# slider.net
KiCad netlist of a schematic drawn in EAGLE
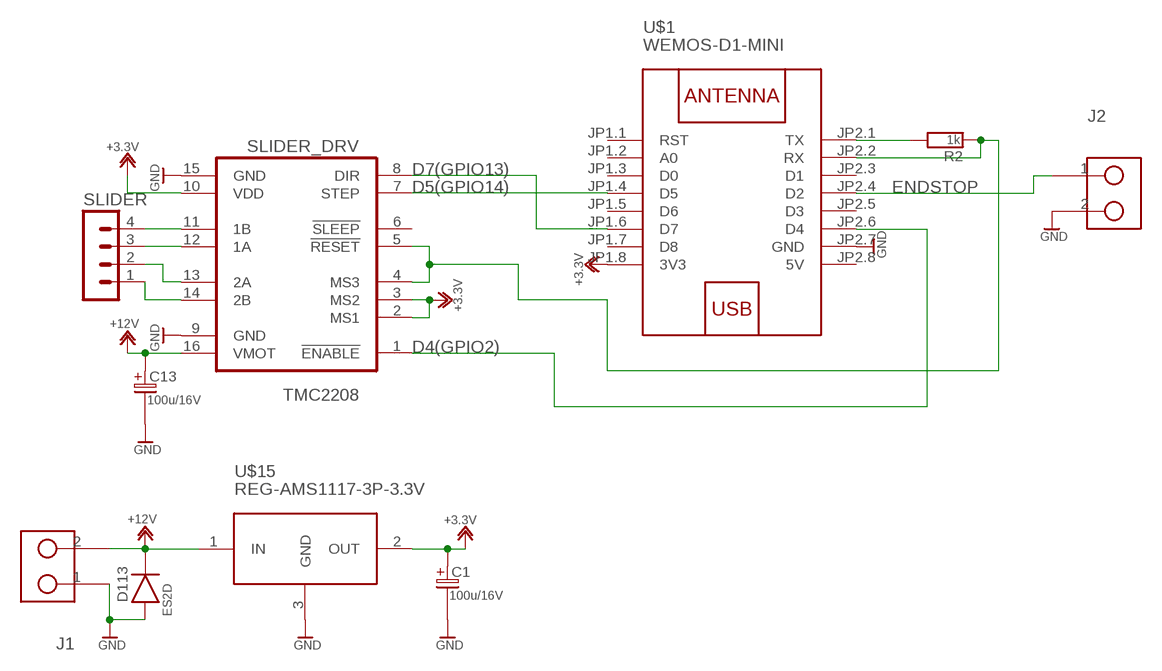
[diagram p0: schematic, sheet 1]

(export (version "E")
  (design (tool "Eeschema 10.0.6"))
  (components
    (comp (ref "C1")
      (value "100u/16V")
      (footprint "eagle-import:ES-3,5_8")
      (libsource (lib "eagle-import") (part "C-EL-3,5/8"))
    )
    (comp (ref "C13")
      (value "100u/16V")
      (footprint "eagle-import:ES-3,5_8")
      (libsource (lib "eagle-import") (part "C-EL-3,5/8"))
    )
    (comp (ref "D113")
      (value "ES2D")
      (footprint "eagle-import:SMB")
      (libsource (lib "eagle-import") (part "DIODESMB"))
    )
    (comp (ref "J1")
      (value "GMKDS-2")
      (footprint "eagle-import:GMKDS1,5")
      (libsource (lib "eagle-import") (part "GMKDS-2"))
    )
    (comp (ref "J2")
      (value "GMKDS-2")
      (footprint "eagle-import:GMKDS1,5")
      (libsource (lib "eagle-import") (part "GMKDS-2"))
    )
    (comp (ref "R2")
      (value "1k")
      (footprint "eagle-import:0805")
      (libsource (lib "eagle-import") (part "RES-0805"))
    )
    (comp (ref "SLIDER")
      (value "MA04-1")
      (footprint "eagle-import:MA04-1")
      (libsource (lib "eagle-import") (part "MA04-1"))
    )
    (comp (ref "SLIDER_DRV")
      (value "TMC2208")
      (footprint "eagle-import:POLOLULU2128")
      (libsource (lib "eagle-import") (part "POLOLULU2128"))
    )
    (comp (ref "U$1")
      (value "WEMOS-D1-MINI")
      (footprint "eagle-import:WEMOS-D1-MINI")
      (libsource (lib "eagle-import") (part "WEMOS-D1-MINI"))
    )
    (comp (ref "U$15")
      (value "REG-AMS1117-3P-3.3V")
      (footprint "eagle-import:REG-AMS1117-3P")
      (libsource (lib "eagle-import") (part "REG-AMS1117-3P-3.3V"))
    )
  )
  (nets
    (net (code "1") (name "+3.3V") (class "Default")
      (node (ref "C1") (pin "1") (pinfunction "1_1") (pintype "passive"))
      (node (ref "SLIDER_DRV") (pin "10") (pinfunction "VDD_10") (pintype "power_in"))
      (node (ref "SLIDER_DRV") (pin "2") (pinfunction "MS1_2") (pintype "input"))
      (node (ref "SLIDER_DRV") (pin "3") (pinfunction "MS2_3") (pintype "input"))
      (node (ref "U$1") (pin "JP1.8") (pinfunction "3V3_JP1.8") (pintype "power_in"))
      (node (ref "U$15") (pin "2") (pinfunction "OUT_2") (pintype "bidirectional"))
    )
    (net (code "2") (name "+12V") (class "Default")
      (node (ref "C13") (pin "1") (pinfunction "1_1") (pintype "passive"))
      (node (ref "D113") (pin "2") (pinfunction "K_2") (pintype "passive"))
      (node (ref "J1") (pin "2") (pinfunction "2_2") (pintype "passive"))
      (node (ref "SLIDER_DRV") (pin "16") (pinfunction "VMOT_16") (pintype "power_in"))
      (node (ref "U$15") (pin "1") (pinfunction "IN_1") (pintype "bidirectional"))
    )
    (net (code "3") (name "/5V") (class "Default")
      (node (ref "U$1") (pin "JP2.8") (pinfunction "5V_JP2.8") (pintype "power_in"))
    )
    (net (code "4") (name "/D4(GPIO2)") (class "Default")
      (node (ref "SLIDER_DRV") (pin "1") (pinfunction "~{ENABLE}_1") (pintype "input"))
      (node (ref "U$1") (pin "JP2.6") (pinfunction "D4_JP2.6") (pintype "bidirectional"))
    )
    (net (code "5") (name "/D5(GPIO14)") (class "Default")
      (node (ref "SLIDER_DRV") (pin "7") (pinfunction "STEP_7") (pintype "input"))
      (node (ref "U$1") (pin "JP1.4") (pinfunction "D5_JP1.4") (pintype "bidirectional"))
    )
    (net (code "6") (name "/D7(GPIO13)") (class "Default")
      (node (ref "SLIDER_DRV") (pin "8") (pinfunction "DIR_8") (pintype "input"))
      (node (ref "U$1") (pin "JP1.6") (pinfunction "D7_JP1.6") (pintype "bidirectional"))
    )
    (net (code "7") (name "/ENDSTOP") (class "Default")
      (node (ref "J2") (pin "1") (pinfunction "1_1") (pintype "passive"))
      (node (ref "U$1") (pin "JP2.4") (pinfunction "D2_JP2.4") (pintype "bidirectional"))
    )
    (net (code "8") (name "GND") (class "Default")
      (node (ref "C1") (pin "2") (pinfunction "2_2") (pintype "passive"))
      (node (ref "C13") (pin "2") (pinfunction "2_2") (pintype "passive"))
      (node (ref "D113") (pin "1") (pinfunction "A_1") (pintype "passive"))
      (node (ref "J1") (pin "1") (pinfunction "1_1") (pintype "passive"))
      (node (ref "J2") (pin "2") (pinfunction "2_2") (pintype "passive"))
      (node (ref "SLIDER_DRV") (pin "15") (pinfunction "GND_15") (pintype "power_in"))
      (node (ref "SLIDER_DRV") (pin "9") (pinfunction "GND_9") (pintype "power_in"))
      (node (ref "U$1") (pin "JP2.7") (pinfunction "GND_JP2.7") (pintype "power_in"))
      (node (ref "U$15") (pin "3") (pinfunction "GND_3") (pintype "bidirectional"))
    )
    (net (code "9") (name "Net-(SLIDER_DRV-1A)") (class "Default")
      (node (ref "SLIDER") (pin "3") (pinfunction "3_3") (pintype "passive"))
      (node (ref "SLIDER_DRV") (pin "12") (pinfunction "1A_12") (pintype "output"))
    )
    (net (code "10") (name "Net-(SLIDER_DRV-1B)") (class "Default")
      (node (ref "SLIDER") (pin "4") (pinfunction "4_4") (pintype "passive"))
      (node (ref "SLIDER_DRV") (pin "11") (pinfunction "1B_11") (pintype "output"))
    )
    (net (code "11") (name "Net-(SLIDER_DRV-2A)") (class "Default")
      (node (ref "SLIDER") (pin "2") (pinfunction "2_2") (pintype "passive"))
      (node (ref "SLIDER_DRV") (pin "13") (pinfunction "2A_13") (pintype "output"))
    )
    (net (code "12") (name "Net-(SLIDER_DRV-2B)") (class "Default")
      (node (ref "SLIDER") (pin "1") (pinfunction "1_1") (pintype "passive"))
      (node (ref "SLIDER_DRV") (pin "14") (pinfunction "2B_14") (pintype "output"))
    )
    (net (code "13") (name "Net-(SLIDER_DRV-MS3)") (class "Default")
      (node (ref "R2") (pin "1") (pinfunction "1_1") (pintype "passive"))
      (node (ref "SLIDER_DRV") (pin "4") (pinfunction "MS3_4") (pintype "input"))
      (node (ref "SLIDER_DRV") (pin "5") (pinfunction "~{RESET}_5") (pintype "input"))
      (node (ref "U$1") (pin "JP2.2") (pinfunction "RX_JP2.2") (pintype "bidirectional"))
    )
    (net (code "14") (name "Net-(U$1-TX)") (class "Default")
      (node (ref "R2") (pin "2") (pinfunction "2_2") (pintype "passive"))
      (node (ref "U$1") (pin "JP2.1") (pinfunction "TX_JP2.1") (pintype "bidirectional"))
    )
    (net (code "15") (name "unconnected-(SLIDER_DRV-~{SLEEP}-Pad6)") (class "Default")
      (node (ref "SLIDER_DRV") (pin "6") (pinfunction "~{SLEEP}_6") (pintype "input"))
    )
    (net (code "16") (name "unconnected-(U$1-A0-PadJP1.2)") (class "Default")
      (node (ref "U$1") (pin "JP1.2") (pinfunction "A0_JP1.2") (pintype "bidirectional"))
    )
    (net (code "17") (name "unconnected-(U$1-D0-PadJP1.3)") (class "Default")
      (node (ref "U$1") (pin "JP1.3") (pinfunction "D0_JP1.3") (pintype "bidirectional"))
    )
    (net (code "18") (name "unconnected-(U$1-D1-PadJP2.3)") (class "Default")
      (node (ref "U$1") (pin "JP2.3") (pinfunction "D1_JP2.3") (pintype "bidirectional"))
    )
    (net (code "19") (name "unconnected-(U$1-D3-PadJP2.5)") (class "Default")
      (node (ref "U$1") (pin "JP2.5") (pinfunction "D3_JP2.5") (pintype "bidirectional"))
    )
    (net (code "20") (name "unconnected-(U$1-D6-PadJP1.5)") (class "Default")
      (node (ref "U$1") (pin "JP1.5") (pinfunction "D6_JP1.5") (pintype "bidirectional"))
    )
    (net (code "21") (name "unconnected-(U$1-D8-PadJP1.7)") (class "Default")
      (node (ref "U$1") (pin "JP1.7") (pinfunction "D8_JP1.7") (pintype "bidirectional"))
    )
    (net (code "22") (name "unconnected-(U$1-RST-PadJP1.1)") (class "Default")
      (node (ref "U$1") (pin "JP1.1") (pinfunction "RST_JP1.1") (pintype "bidirectional"))
    )
  )
)
